# IO_Systems.net
KiCad netlist of a schematic drawn in Altium Designer
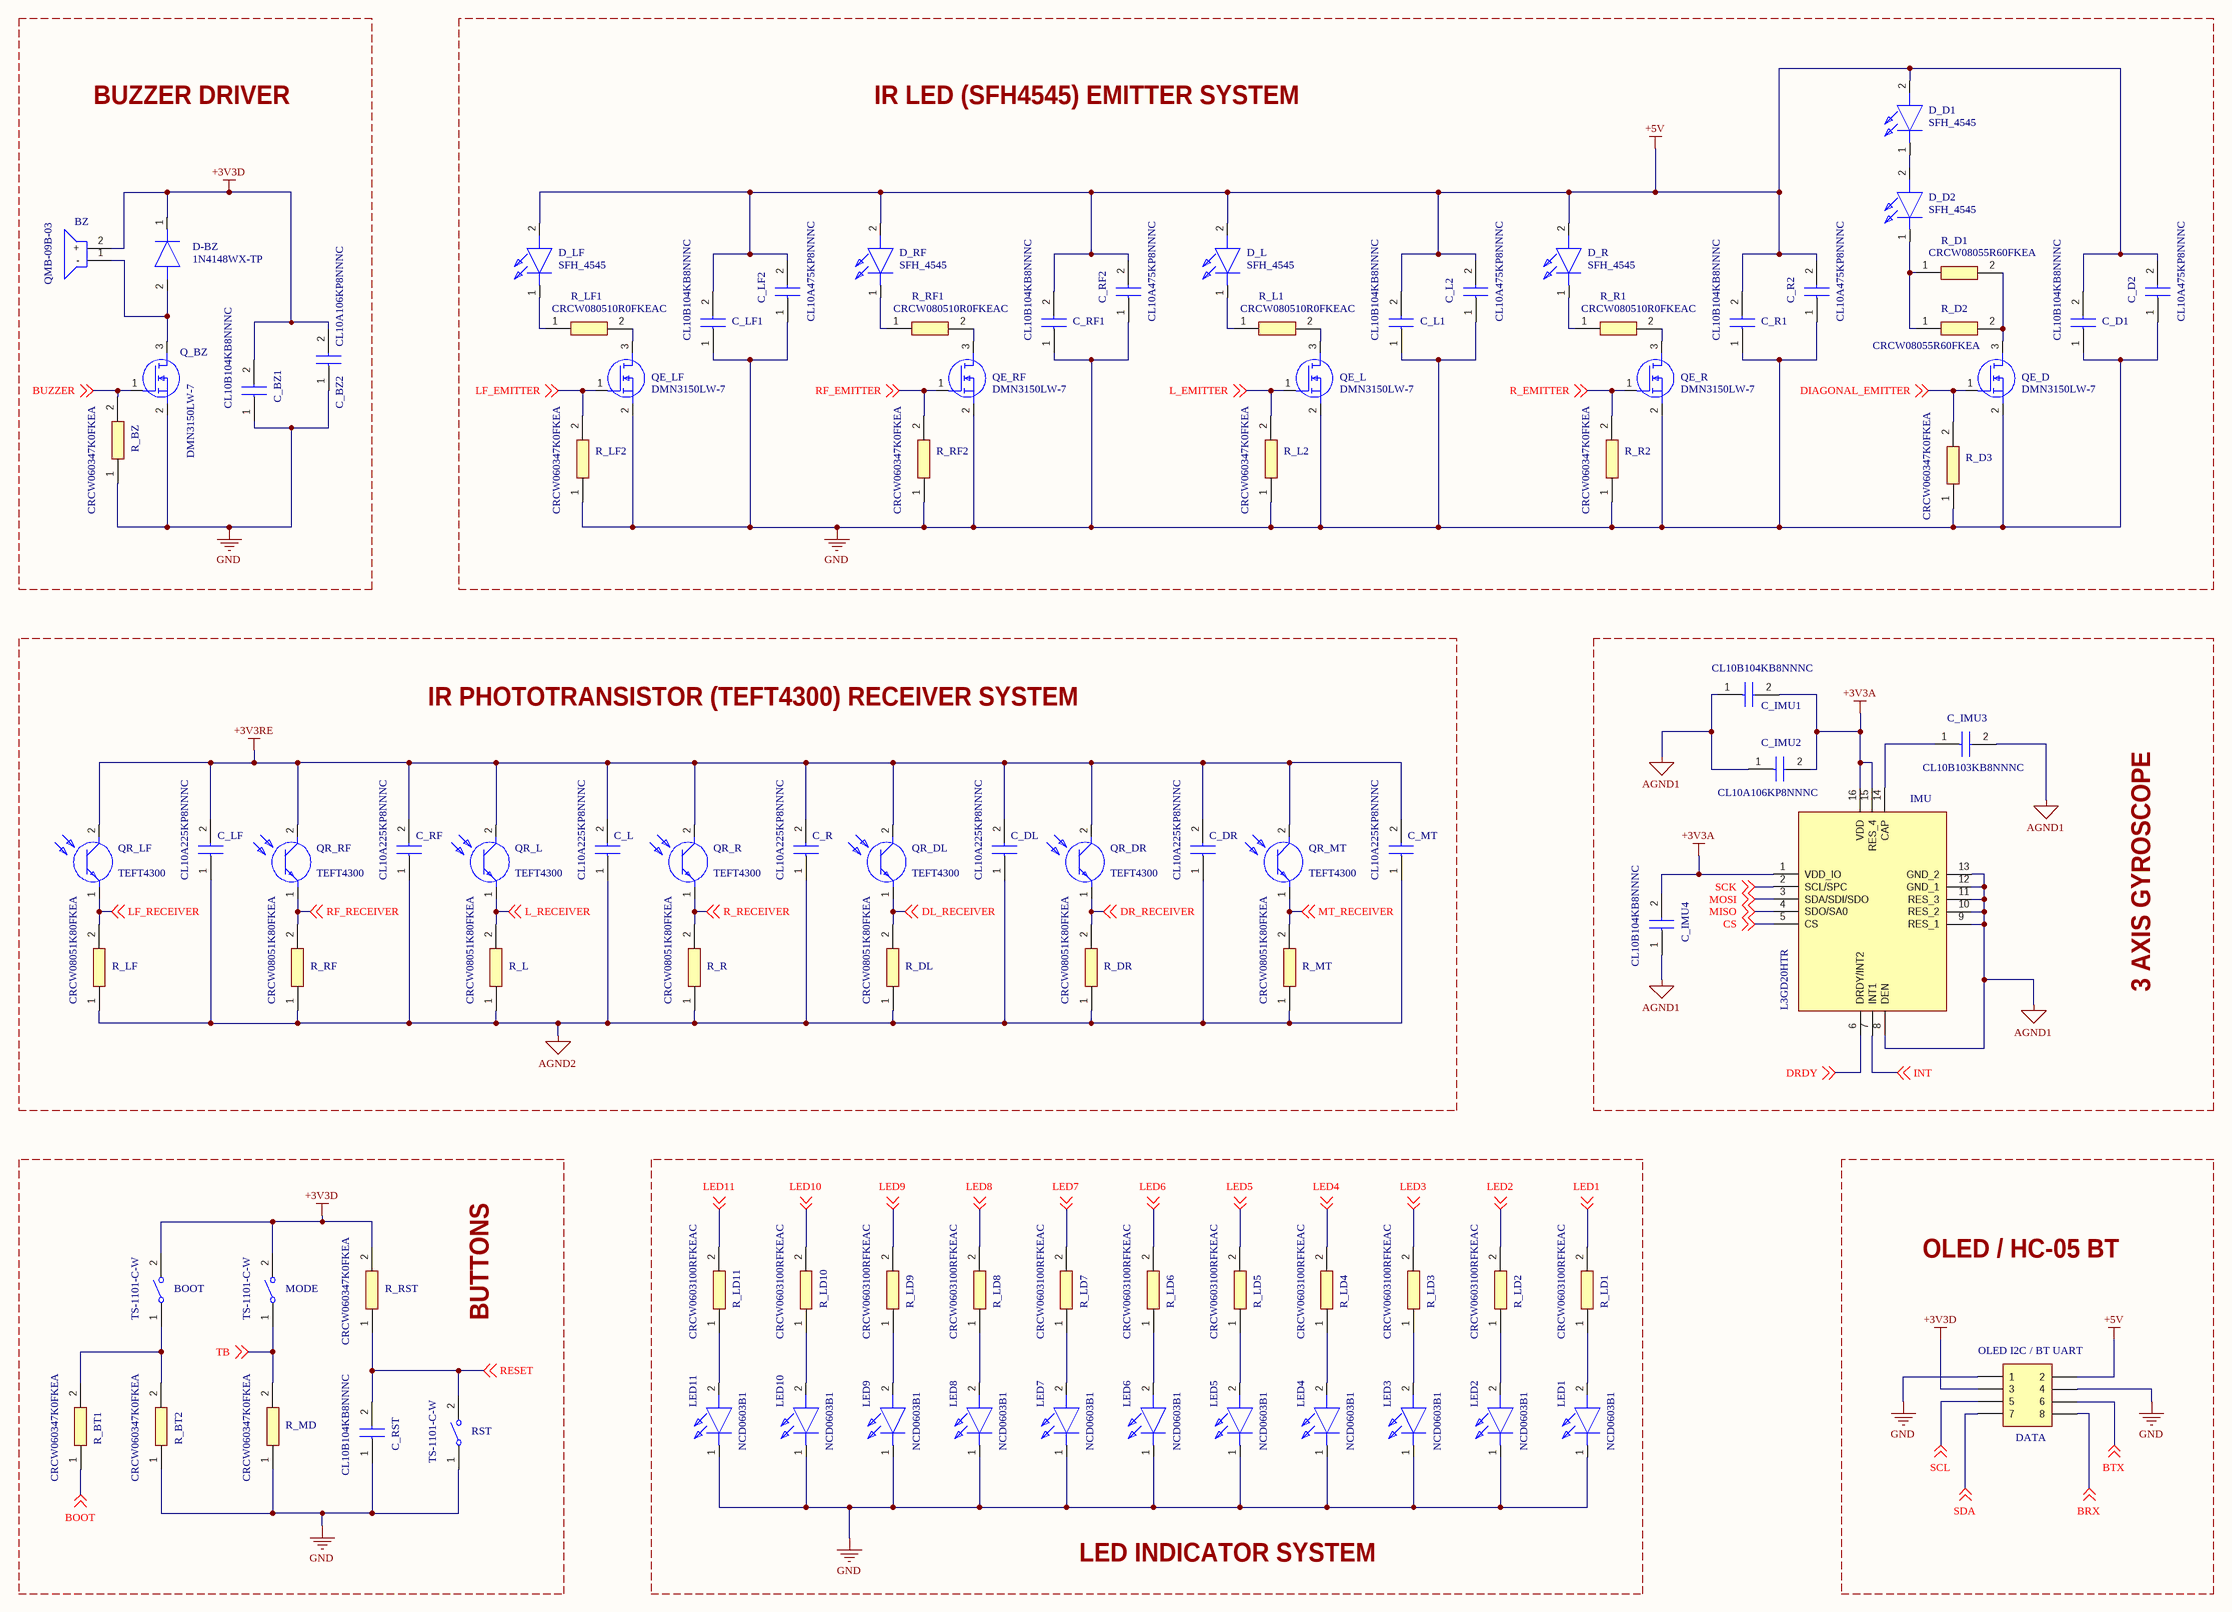
[diagram p0: IO Systems.SchDoc]

(export (version "E")
  (design (tool "Eeschema 10.0.6"))
  (components
    (comp (ref "BOOT")
      (value "TS-1101-C-W")
      (footprint "TECO-FSMSM-2_V")
      (fields (field (name "MANUFACTURER") "TE Connectivity"))
      (libsource (lib "Altium Content Vault") (part "SW-SPST-2_C"))
    )
    (comp (ref "BZ")
      (value "QMB-09B-03")
      (footprint "SamacSys:CST931AP")
      (description "85dB Passive (external drive) Electromagnetic Type 2.7kHz Plugin,D=9mm Buzzers ROHS")
      (fields
        (field (name "MANUFACTURER_PART_NUMBER") "CST-931AP")
        (field (name "MOUSER PART NUMBER") "490-CST-931AP")
      )
      (libsource (lib "*") (part "CST-931AP"))
    )
    (comp (ref "C_BZ1")
      (value "CL10B104KB8NNNC")
      (footprint "SamacSys:CAPC1608X90N")
      (description "Capacitor")
      (fields (field (name "MOUSER PART NUMBER") "187-CL10B104KB8NNNC"))
      (libsource (lib "*") (part "CL10B104KB8NNNC"))
    )
    (comp (ref "C_BZ2")
      (value "CL10A106KP8NNNC")
      (footprint "SamacSys:CAPC1608X90N")
      (description "Capacitor")
      (fields (field (name "MOUSER PART NUMBER") "187-CL10A106KP8NNNC"))
      (libsource (lib "*") (part "CL10A106KP8NNNC"))
    )
    (comp (ref "C_D1")
      (value "CL10B104KB8NNNC")
      (footprint "SamacSys:CAPC1608X90N")
      (description "Capacitor")
      (fields (field (name "MOUSER PART NUMBER") "187-CL10B104KB8NNNC"))
      (libsource (lib "*") (part "CL10B104KB8NNNC"))
    )
    (comp (ref "C_D2")
      (value "CL10A475KP8NNNC")
      (footprint "SamacSys:CAPC1608X90N")
      (description "Capacitor")
      (fields (field (name "MOUSER PART NUMBER") "187-CL10A475KP8NNNC"))
      (libsource (lib "*") (part "CL10A475KP8NNNC"))
    )
    (comp (ref "C_DL")
      (value "CL10A225KP8NNNC")
      (footprint "SamacSys:CAPC1608X90N")
      (description "Capacitor")
      (fields (field (name "MOUSER PART NUMBER") "187-CL10A225KP8NNNC"))
      (libsource (lib "*") (part "CL10A225KP8NNNC"))
    )
    (comp (ref "C_DR")
      (value "CL10A225KP8NNNC")
      (footprint "SamacSys:CAPC1608X90N")
      (description "Capacitor")
      (fields (field (name "MOUSER PART NUMBER") "187-CL10A225KP8NNNC"))
      (libsource (lib "*") (part "CL10A225KP8NNNC"))
    )
    (comp (ref "C_IMU1")
      (value "CL10B104KB8NNNC")
      (footprint "SamacSys:CAPC1608X90N")
      (description "Capacitor")
      (fields (field (name "MOUSER PART NUMBER") "187-CL10B104KB8NNNC"))
      (libsource (lib "*") (part "CL10B104KB8NNNC"))
    )
    (comp (ref "C_IMU2")
      (value "CL10A106KP8NNNC")
      (footprint "SamacSys:CAPC1608X90N")
      (description "Capacitor")
      (fields (field (name "MOUSER PART NUMBER") "187-CL10A106KP8NNNC"))
      (libsource (lib "*") (part "CL10A106KP8NNNC"))
    )
    (comp (ref "C_IMU3")
      (value "CL10B103KB8NNNC")
      (footprint "SamacSys:CAPC1608X90N")
      (description "Capacitor")
      (fields (field (name "MOUSER PART NUMBER") "187-CL10B103KB8NNNC"))
      (libsource (lib "*") (part "CL10B103KB8NNNC"))
    )
    (comp (ref "C_IMU4")
      (value "CL10B104KB8NNNC")
      (footprint "SamacSys:CAPC1608X90N")
      (description "Capacitor")
      (fields (field (name "MOUSER PART NUMBER") "187-CL10B104KB8NNNC"))
      (libsource (lib "*") (part "CL10B104KB8NNNC"))
    )
    (comp (ref "C_L")
      (value "CL10A225KP8NNNC")
      (footprint "SamacSys:CAPC1608X90N")
      (description "Capacitor")
      (fields (field (name "MOUSER PART NUMBER") "187-CL10A225KP8NNNC"))
      (libsource (lib "*") (part "CL10A225KP8NNNC"))
    )
    (comp (ref "C_L1")
      (value "CL10B104KB8NNNC")
      (footprint "SamacSys:CAPC1608X90N")
      (description "Capacitor")
      (fields (field (name "MOUSER PART NUMBER") "187-CL10B104KB8NNNC"))
      (libsource (lib "*") (part "CL10B104KB8NNNC"))
    )
    (comp (ref "C_L2")
      (value "CL10A475KP8NNNC")
      (footprint "SamacSys:CAPC1608X90N")
      (description "Capacitor")
      (fields (field (name "MOUSER PART NUMBER") "187-CL10A475KP8NNNC"))
      (libsource (lib "*") (part "CL10A475KP8NNNC"))
    )
    (comp (ref "C_LF")
      (value "CL10A225KP8NNNC")
      (footprint "SamacSys:CAPC1608X90N")
      (description "Capacitor")
      (fields (field (name "MOUSER PART NUMBER") "187-CL10A225KP8NNNC"))
      (libsource (lib "*") (part "CL10A225KP8NNNC"))
    )
    (comp (ref "C_LF1")
      (value "CL10B104KB8NNNC")
      (footprint "SamacSys:CAPC1608X90N")
      (description "Capacitor")
      (fields (field (name "MOUSER PART NUMBER") "187-CL10B104KB8NNNC"))
      (libsource (lib "*") (part "CL10B104KB8NNNC"))
    )
    (comp (ref "C_LF2")
      (value "CL10A475KP8NNNC")
      (footprint "SamacSys:CAPC1608X90N")
      (description "Capacitor")
      (fields (field (name "MOUSER PART NUMBER") "187-CL10A475KP8NNNC"))
      (libsource (lib "*") (part "CL10A475KP8NNNC"))
    )
    (comp (ref "C_MT")
      (value "CL10A225KP8NNNC")
      (footprint "SamacSys:CAPC1608X90N")
      (description "Capacitor")
      (fields (field (name "MOUSER PART NUMBER") "187-CL10A225KP8NNNC"))
      (libsource (lib "*") (part "CL10A225KP8NNNC"))
    )
    (comp (ref "C_R")
      (value "CL10A225KP8NNNC")
      (footprint "SamacSys:CAPC1608X90N")
      (description "Capacitor")
      (fields (field (name "MOUSER PART NUMBER") "187-CL10A225KP8NNNC"))
      (libsource (lib "*") (part "CL10A225KP8NNNC"))
    )
    (comp (ref "C_R1")
      (value "CL10B104KB8NNNC")
      (footprint "SamacSys:CAPC1608X90N")
      (description "Capacitor")
      (fields (field (name "MOUSER PART NUMBER") "187-CL10B104KB8NNNC"))
      (libsource (lib "*") (part "CL10B104KB8NNNC"))
    )
    (comp (ref "C_R2")
      (value "CL10A475KP8NNNC")
      (footprint "SamacSys:CAPC1608X90N")
      (description "Capacitor")
      (fields (field (name "MOUSER PART NUMBER") "187-CL10A475KP8NNNC"))
      (libsource (lib "*") (part "CL10A475KP8NNNC"))
    )
    (comp (ref "C_RF")
      (value "CL10A225KP8NNNC")
      (footprint "SamacSys:CAPC1608X90N")
      (description "Capacitor")
      (fields (field (name "MOUSER PART NUMBER") "187-CL10A225KP8NNNC"))
      (libsource (lib "*") (part "CL10A225KP8NNNC"))
    )
    (comp (ref "C_RF1")
      (value "CL10B104KB8NNNC")
      (footprint "SamacSys:CAPC1608X90N")
      (description "Capacitor")
      (fields (field (name "MOUSER PART NUMBER") "187-CL10B104KB8NNNC"))
      (libsource (lib "*") (part "CL10B104KB8NNNC"))
    )
    (comp (ref "C_RF2")
      (value "CL10A475KP8NNNC")
      (footprint "SamacSys:CAPC1608X90N")
      (description "Capacitor")
      (fields (field (name "MOUSER PART NUMBER") "187-CL10A475KP8NNNC"))
      (libsource (lib "*") (part "CL10A475KP8NNNC"))
    )
    (comp (ref "C_RST")
      (value "CL10B104KB8NNNC")
      (footprint "SamacSys:CAPC1608X90N")
      (description "Capacitor")
      (fields (field (name "MOUSER PART NUMBER") "187-CL10B104KB8NNNC"))
      (libsource (lib "*") (part "CL10B104KB8NNNC"))
    )
    (comp (ref "D-BZ")
      (value "1N4148WX-TP")
      (footprint "SamacSys:SOD2512X115N")
      (description "Diode")
      (fields (field (name "MOUSER PART NUMBER") "833-1N4148WX-TP"))
      (libsource (lib "*") (part "1N4148WX-TP"))
    )
    (comp (ref "DATA")
      (value "OLED I2C / BT UART")
      (footprint "MY_FE04-2")
      (description "Header, 8-Pin, Dual row")
      (fields (field (name "ASID PART NUMBER") "Header 4X2-AS"))
      (libsource (lib "Mylib+Rev+4") (part "Header 4X2"))
    )
    (comp (ref "D_D1")
      (value "SFH_4545")
      (footprint "SamacSys:SFH4545")
      (description "LED")
      (fields
        (field (name "MANUFACTURER_PART_NUMBER") "SFH 4545")
        (field (name "MOUSER PART NUMBER") "720-SFH4545")
      )
      (libsource (lib "*") (part "SFH_4545"))
    )
    (comp (ref "D_D2")
      (value "SFH_4545")
      (footprint "SamacSys:SFH4545")
      (description "LED")
      (fields
        (field (name "MANUFACTURER_PART_NUMBER") "SFH 4545")
        (field (name "MOUSER PART NUMBER") "720-SFH4545")
      )
      (libsource (lib "*") (part "SFH_4545"))
    )
    (comp (ref "D_L")
      (value "SFH_4545")
      (footprint "SamacSys:SFH4545")
      (description "LED")
      (fields
        (field (name "MANUFACTURER_PART_NUMBER") "SFH 4545")
        (field (name "MOUSER PART NUMBER") "720-SFH4545")
      )
      (libsource (lib "*") (part "SFH_4545"))
    )
    (comp (ref "D_LF")
      (value "SFH_4545")
      (footprint "SamacSys:SFH4545")
      (description "LED")
      (fields
        (field (name "MANUFACTURER_PART_NUMBER") "SFH 4545")
        (field (name "MOUSER PART NUMBER") "720-SFH4545")
      )
      (libsource (lib "*") (part "SFH_4545"))
    )
    (comp (ref "D_R")
      (value "SFH_4545")
      (footprint "SamacSys:SFH4545")
      (description "LED")
      (fields
        (field (name "MANUFACTURER_PART_NUMBER") "SFH 4545")
        (field (name "MOUSER PART NUMBER") "720-SFH4545")
      )
      (libsource (lib "*") (part "SFH_4545"))
    )
    (comp (ref "D_RF")
      (value "SFH_4545")
      (footprint "SamacSys:SFH4545")
      (description "LED")
      (fields
        (field (name "MANUFACTURER_PART_NUMBER") "SFH 4545")
        (field (name "MOUSER PART NUMBER") "720-SFH4545")
      )
      (libsource (lib "*") (part "SFH_4545"))
    )
    (comp (ref "IMU")
      (value "L3GD20HTR")
      (footprint "SamacSys:H3LIS100DLTR")
      (description "Integrated Circuit")
      (fields (field (name "MOUSER PART NUMBER") "511-L3GD20HTR"))
      (libsource (lib "*") (part "L3GD20HTR"))
    )
    (comp (ref "LED1")
      (value "NCD0603B1")
      (footprint "SamacSys:LEDC1608X40N")
      (fields
        (field (name "MANUFACTURER_PART_NUMBER") "LB Q39E-L2OO-35-1")
        (field (name "MOUSER PART NUMBER") "720-LBQ39EL2N2351")
      )
      (libsource (lib "*") (part "LB_Q39E-L2OO-35-1"))
    )
    (comp (ref "LED2")
      (value "NCD0603B1")
      (footprint "SamacSys:LEDC1608X40N")
      (fields
        (field (name "MANUFACTURER_PART_NUMBER") "LB Q39E-L2OO-35-1")
        (field (name "MOUSER PART NUMBER") "720-LBQ39EL2N2351")
      )
      (libsource (lib "*") (part "LB_Q39E-L2OO-35-1"))
    )
    (comp (ref "LED3")
      (value "NCD0603B1")
      (footprint "SamacSys:LEDC1608X40N")
      (fields
        (field (name "MANUFACTURER_PART_NUMBER") "LB Q39E-L2OO-35-1")
        (field (name "MOUSER PART NUMBER") "720-LBQ39EL2N2351")
      )
      (libsource (lib "*") (part "LB_Q39E-L2OO-35-1"))
    )
    (comp (ref "LED4")
      (value "NCD0603B1")
      (footprint "SamacSys:LEDC1608X40N")
      (fields
        (field (name "MANUFACTURER_PART_NUMBER") "LB Q39E-L2OO-35-1")
        (field (name "MOUSER PART NUMBER") "720-LBQ39EL2N2351")
      )
      (libsource (lib "*") (part "LB_Q39E-L2OO-35-1"))
    )
    (comp (ref "LED5")
      (value "NCD0603B1")
      (footprint "SamacSys:LEDC1608X40N")
      (fields
        (field (name "MANUFACTURER_PART_NUMBER") "LB Q39E-L2OO-35-1")
        (field (name "MOUSER PART NUMBER") "720-LBQ39EL2N2351")
      )
      (libsource (lib "*") (part "LB_Q39E-L2OO-35-1"))
    )
    (comp (ref "LED6")
      (value "NCD0603B1")
      (footprint "SamacSys:LEDC1608X40N")
      (fields
        (field (name "MANUFACTURER_PART_NUMBER") "LB Q39E-L2OO-35-1")
        (field (name "MOUSER PART NUMBER") "720-LBQ39EL2N2351")
      )
      (libsource (lib "*") (part "LB_Q39E-L2OO-35-1"))
    )
    (comp (ref "LED7")
      (value "NCD0603B1")
      (footprint "SamacSys:LEDC1608X40N")
      (fields
        (field (name "MANUFACTURER_PART_NUMBER") "LB Q39E-L2OO-35-1")
        (field (name "MOUSER PART NUMBER") "720-LBQ39EL2N2351")
      )
      (libsource (lib "*") (part "LB_Q39E-L2OO-35-1"))
    )
    (comp (ref "LED8")
      (value "NCD0603B1")
      (footprint "SamacSys:LEDC1608X40N")
      (fields
        (field (name "MANUFACTURER_PART_NUMBER") "LB Q39E-L2OO-35-1")
        (field (name "MOUSER PART NUMBER") "720-LBQ39EL2N2351")
      )
      (libsource (lib "*") (part "LB_Q39E-L2OO-35-1"))
    )
    (comp (ref "LED9")
      (value "NCD0603B1")
      (footprint "SamacSys:LEDC1608X40N")
      (fields
        (field (name "MANUFACTURER_PART_NUMBER") "LB Q39E-L2OO-35-1")
        (field (name "MOUSER PART NUMBER") "720-LBQ39EL2N2351")
      )
      (libsource (lib "*") (part "LB_Q39E-L2OO-35-1"))
    )
    (comp (ref "LED10")
      (value "NCD0603B1")
      (footprint "SamacSys:LEDC1608X40N")
      (fields
        (field (name "MANUFACTURER_PART_NUMBER") "LB Q39E-L2OO-35-1")
        (field (name "MOUSER PART NUMBER") "720-LBQ39EL2N2351")
      )
      (libsource (lib "*") (part "LB_Q39E-L2OO-35-1"))
    )
    (comp (ref "LED11")
      (value "NCD0603B1")
      (footprint "SamacSys:LEDC1608X40N")
      (fields
        (field (name "MANUFACTURER_PART_NUMBER") "LB Q39E-L2OO-35-1")
        (field (name "MOUSER PART NUMBER") "720-LBQ39EL2N2351")
      )
      (libsource (lib "*") (part "LB_Q39E-L2OO-35-1"))
    )
    (comp (ref "MODE")
      (value "TS-1101-C-W")
      (footprint "TECO-FSMSM-2_V")
      (fields (field (name "MANUFACTURER") "TE Connectivity"))
      (libsource (lib "Altium Content Vault") (part "SW-SPST-2_C"))
    )
    (comp (ref "QE_D")
      (value "DMN3150LW-7")
      (footprint "SamacSys:SOT65P210X110-3N")
      (description "MOSFET (N-Channel)")
      (fields (field (name "MOUSER PART NUMBER") "621-DMN3150LW-7"))
      (libsource (lib "*") (part "DMN3150LW-7"))
    )
    (comp (ref "QE_L")
      (value "DMN3150LW-7")
      (footprint "SamacSys:SOT65P210X110-3N")
      (description "MOSFET (N-Channel)")
      (fields (field (name "MOUSER PART NUMBER") "621-DMN3150LW-7"))
      (libsource (lib "*") (part "DMN3150LW-7"))
    )
    (comp (ref "QE_LF")
      (value "DMN3150LW-7")
      (footprint "SamacSys:SOT65P210X110-3N")
      (description "MOSFET (N-Channel)")
      (fields (field (name "MOUSER PART NUMBER") "621-DMN3150LW-7"))
      (libsource (lib "*") (part "DMN3150LW-7"))
    )
    (comp (ref "QE_R")
      (value "DMN3150LW-7")
      (footprint "SamacSys:SOT65P210X110-3N")
      (description "MOSFET (N-Channel)")
      (fields (field (name "MOUSER PART NUMBER") "621-DMN3150LW-7"))
      (libsource (lib "*") (part "DMN3150LW-7"))
    )
    (comp (ref "QE_RF")
      (value "DMN3150LW-7")
      (footprint "SamacSys:SOT65P210X110-3N")
      (description "MOSFET (N-Channel)")
      (fields (field (name "MOUSER PART NUMBER") "621-DMN3150LW-7"))
      (libsource (lib "*") (part "DMN3150LW-7"))
    )
    (comp (ref "QR_DL")
      (value "TEFT4300")
      (footprint "SamacSys:TEFT4300")
      (description "Phototransistor")
      (fields (field (name "MOUSER PART NUMBER") "782-TEFT4300"))
      (libsource (lib "*") (part "TEFT4300"))
    )
    (comp (ref "QR_DR")
      (value "TEFT4300")
      (footprint "SamacSys:TEFT4300")
      (description "Phototransistor")
      (fields (field (name "MOUSER PART NUMBER") "782-TEFT4300"))
      (libsource (lib "*") (part "TEFT4300"))
    )
    (comp (ref "QR_L")
      (value "TEFT4300")
      (footprint "SamacSys:TEFT4300")
      (description "Phototransistor")
      (fields (field (name "MOUSER PART NUMBER") "782-TEFT4300"))
      (libsource (lib "*") (part "TEFT4300"))
    )
    (comp (ref "QR_LF")
      (value "TEFT4300")
      (footprint "SamacSys:TEFT4300")
      (description "Phototransistor")
      (fields (field (name "MOUSER PART NUMBER") "782-TEFT4300"))
      (libsource (lib "*") (part "TEFT4300"))
    )
    (comp (ref "QR_MT")
      (value "TEFT4300")
      (footprint "SamacSys:TEFT4300")
      (description "Phototransistor")
      (fields (field (name "MOUSER PART NUMBER") "782-TEFT4300"))
      (libsource (lib "*") (part "TEFT4300"))
    )
    (comp (ref "QR_R")
      (value "TEFT4300")
      (footprint "SamacSys:TEFT4300")
      (description "Phototransistor")
      (fields (field (name "MOUSER PART NUMBER") "782-TEFT4300"))
      (libsource (lib "*") (part "TEFT4300"))
    )
    (comp (ref "QR_RF")
      (value "TEFT4300")
      (footprint "SamacSys:TEFT4300")
      (description "Phototransistor")
      (fields (field (name "MOUSER PART NUMBER") "782-TEFT4300"))
      (libsource (lib "*") (part "TEFT4300"))
    )
    (comp (ref "Q_BZ")
      (value "DMN3150LW-7")
      (footprint "SamacSys:SOT65P210X110-3N")
      (description "MOSFET (N-Channel)")
      (fields (field (name "MOUSER PART NUMBER") "621-DMN3150LW-7"))
      (libsource (lib "*") (part "DMN3150LW-7"))
    )
    (comp (ref "RST")
      (value "TS-1101-C-W")
      (footprint "TECO-FSMSM-2_V")
      (fields (field (name "MANUFACTURER") "TE Connectivity"))
      (libsource (lib "Altium Content Vault") (part "SW-SPST-2_C"))
    )
    (comp (ref "R_BT1")
      (value "CRCW060347K0FKEA")
      (footprint "SamacSys:RESC1608X50N")
      (description "Resistor")
      (fields (field (name "MOUSER PART NUMBER") "71-CRCW0603-47K-E3"))
      (libsource (lib "*") (part "CRCW060347K0FKEA"))
    )
    (comp (ref "R_BT2")
      (value "CRCW060347K0FKEA")
      (footprint "SamacSys:RESC1608X50N")
      (description "Resistor")
      (fields (field (name "MOUSER PART NUMBER") "71-CRCW0603-47K-E3"))
      (libsource (lib "*") (part "CRCW060347K0FKEA"))
    )
    (comp (ref "R_BZ")
      (value "CRCW060347K0FKEA")
      (footprint "SamacSys:RESC1608X50N")
      (description "Resistor")
      (fields (field (name "MOUSER PART NUMBER") "71-CRCW0603-47K-E3"))
      (libsource (lib "*") (part "CRCW060347K0FKEA"))
    )
    (comp (ref "R_D1")
      (value "CRCW08055R60FKEA")
      (footprint "SamacSys:RESC2012X60N")
      (description "Resistor")
      (fields
        (field (name "MANUFACTURER_PART_NUMBER") "CRCW08055R60FKEAHP")
        (field (name "MOUSER PART NUMBER") "71-CRCW08055R60FKEAH")
      )
      (libsource (lib "*") (part "CRCW08055R60FKEAHP"))
    )
    (comp (ref "R_D2")
      (value "CRCW08055R60FKEA")
      (footprint "SamacSys:RESC2012X60N")
      (description "Resistor")
      (fields
        (field (name "MANUFACTURER_PART_NUMBER") "CRCW08055R60FKEAHP")
        (field (name "MOUSER PART NUMBER") "71-CRCW08055R60FKEAH")
      )
      (libsource (lib "*") (part "CRCW08055R60FKEAHP"))
    )
    (comp (ref "R_D3")
      (value "CRCW060347K0FKEA")
      (footprint "SamacSys:RESC1608X50N")
      (description "Resistor")
      (fields (field (name "MOUSER PART NUMBER") "71-CRCW0603-47K-E3"))
      (libsource (lib "*") (part "CRCW060347K0FKEA"))
    )
    (comp (ref "R_DL")
      (value "CRCW08051K80FKEA")
      (footprint "SamacSys:RESC2012X60N")
      (description "Resistor")
      (fields
        (field (name "MANUFACTURER_PART_NUMBER") "CRCW08051K80FKEAC")
        (field (name "MOUSER PART NUMBER") "71-CRCW08051K80FKEAC")
      )
      (libsource (lib "*") (part "CRCW08051K80FKEAC"))
    )
    (comp (ref "R_DR")
      (value "CRCW08051K80FKEA")
      (footprint "SamacSys:RESC2012X60N")
      (description "Resistor")
      (fields
        (field (name "MANUFACTURER_PART_NUMBER") "CRCW08051K80FKEAC")
        (field (name "MOUSER PART NUMBER") "71-CRCW08051K80FKEAC")
      )
      (libsource (lib "*") (part "CRCW08051K80FKEAC"))
    )
    (comp (ref "R_L")
      (value "CRCW08051K80FKEA")
      (footprint "SamacSys:RESC2012X60N")
      (description "Resistor")
      (fields
        (field (name "MANUFACTURER_PART_NUMBER") "CRCW08051K80FKEAC")
        (field (name "MOUSER PART NUMBER") "71-CRCW08051K80FKEAC")
      )
      (libsource (lib "*") (part "CRCW08051K80FKEAC"))
    )
    (comp (ref "R_L1")
      (value "CRCW080510R0FKEAC")
      (footprint "SamacSys:RESC2012X60N")
      (description "Resistor")
      (fields (field (name "MOUSER PART NUMBER") "71-CRCW080510R0FKEAC"))
      (libsource (lib "*") (part "CRCW080510R0FKEAC"))
    )
    (comp (ref "R_L2")
      (value "CRCW060347K0FKEA")
      (footprint "SamacSys:RESC1608X50N")
      (description "Resistor")
      (fields (field (name "MOUSER PART NUMBER") "71-CRCW0603-47K-E3"))
      (libsource (lib "*") (part "CRCW060347K0FKEA"))
    )
    (comp (ref "R_LD1")
      (value "CRCW0603100RFKEAC")
      (footprint "SamacSys:RESC1608X55N")
      (description "Resistor")
      (fields (field (name "MOUSER PART NUMBER") "71-CRCW0603100RFKEAC"))
      (libsource (lib "*") (part "CRCW0603100RFKEAC"))
    )
    (comp (ref "R_LD2")
      (value "CRCW0603100RFKEAC")
      (footprint "SamacSys:RESC1608X55N")
      (description "Resistor")
      (fields (field (name "MOUSER PART NUMBER") "71-CRCW0603100RFKEAC"))
      (libsource (lib "*") (part "CRCW0603100RFKEAC"))
    )
    (comp (ref "R_LD3")
      (value "CRCW0603100RFKEAC")
      (footprint "SamacSys:RESC1608X55N")
      (description "Resistor")
      (fields (field (name "MOUSER PART NUMBER") "71-CRCW0603100RFKEAC"))
      (libsource (lib "*") (part "CRCW0603100RFKEAC"))
    )
    (comp (ref "R_LD4")
      (value "CRCW0603100RFKEAC")
      (footprint "SamacSys:RESC1608X55N")
      (description "Resistor")
      (fields (field (name "MOUSER PART NUMBER") "71-CRCW0603100RFKEAC"))
      (libsource (lib "*") (part "CRCW0603100RFKEAC"))
    )
    (comp (ref "R_LD5")
      (value "CRCW0603100RFKEAC")
      (footprint "SamacSys:RESC1608X55N")
      (description "Resistor")
      (fields (field (name "MOUSER PART NUMBER") "71-CRCW0603100RFKEAC"))
      (libsource (lib "*") (part "CRCW0603100RFKEAC"))
    )
    (comp (ref "R_LD6")
      (value "CRCW0603100RFKEAC")
      (footprint "SamacSys:RESC1608X55N")
      (description "Resistor")
      (fields (field (name "MOUSER PART NUMBER") "71-CRCW0603100RFKEAC"))
      (libsource (lib "*") (part "CRCW0603100RFKEAC"))
    )
    (comp (ref "R_LD7")
      (value "CRCW0603100RFKEAC")
      (footprint "SamacSys:RESC1608X55N")
      (description "Resistor")
      (fields (field (name "MOUSER PART NUMBER") "71-CRCW0603100RFKEAC"))
      (libsource (lib "*") (part "CRCW0603100RFKEAC"))
    )
    (comp (ref "R_LD8")
      (value "CRCW0603100RFKEAC")
      (footprint "SamacSys:RESC1608X55N")
      (description "Resistor")
      (fields (field (name "MOUSER PART NUMBER") "71-CRCW0603100RFKEAC"))
      (libsource (lib "*") (part "CRCW0603100RFKEAC"))
    )
    (comp (ref "R_LD9")
      (value "CRCW0603100RFKEAC")
      (footprint "SamacSys:RESC1608X55N")
      (description "Resistor")
      (fields (field (name "MOUSER PART NUMBER") "71-CRCW0603100RFKEAC"))
      (libsource (lib "*") (part "CRCW0603100RFKEAC"))
    )
    (comp (ref "R_LD10")
      (value "CRCW0603100RFKEAC")
      (footprint "SamacSys:RESC1608X55N")
      (description "Resistor")
      (fields (field (name "MOUSER PART NUMBER") "71-CRCW0603100RFKEAC"))
      (libsource (lib "*") (part "CRCW0603100RFKEAC"))
    )
    (comp (ref "R_LD11")
      (value "CRCW0603100RFKEAC")
      (footprint "SamacSys:RESC1608X55N")
      (description "Resistor")
      (fields (field (name "MOUSER PART NUMBER") "71-CRCW0603100RFKEAC"))
      (libsource (lib "*") (part "CRCW0603100RFKEAC"))
    )
    (comp (ref "R_LF")
      (value "CRCW08051K80FKEA")
      (footprint "SamacSys:RESC2012X60N")
      (description "Resistor")
      (fields
        (field (name "MANUFACTURER_PART_NUMBER") "CRCW08051K80FKEAC")
        (field (name "MOUSER PART NUMBER") "71-CRCW08051K80FKEAC")
      )
      (libsource (lib "*") (part "CRCW08051K80FKEAC"))
    )
    (comp (ref "R_LF1")
      (value "CRCW080510R0FKEAC")
      (footprint "SamacSys:RESC2012X60N")
      (description "Resistor")
      (fields (field (name "MOUSER PART NUMBER") "71-CRCW080510R0FKEAC"))
      (libsource (lib "*") (part "CRCW080510R0FKEAC"))
    )
    (comp (ref "R_LF2")
      (value "CRCW060347K0FKEA")
      (footprint "SamacSys:RESC1608X50N")
      (description "Resistor")
      (fields (field (name "MOUSER PART NUMBER") "71-CRCW0603-47K-E3"))
      (libsource (lib "*") (part "CRCW060347K0FKEA"))
    )
    (comp (ref "R_MD")
      (value "CRCW060347K0FKEA")
      (footprint "SamacSys:RESC1608X50N")
      (description "Resistor")
      (fields (field (name "MOUSER PART NUMBER") "71-CRCW0603-47K-E3"))
      (libsource (lib "*") (part "CRCW060347K0FKEA"))
    )
    (comp (ref "R_MT")
      (value "CRCW08051K80FKEA")
      (footprint "SamacSys:RESC2012X60N")
      (description "Resistor")
      (fields
        (field (name "MANUFACTURER_PART_NUMBER") "CRCW08051K80FKEAC")
        (field (name "MOUSER PART NUMBER") "71-CRCW08051K80FKEAC")
      )
      (libsource (lib "*") (part "CRCW08051K80FKEAC"))
    )
    (comp (ref "R_R")
      (value "CRCW08051K80FKEA")
      (footprint "SamacSys:RESC2012X60N")
      (description "Resistor")
      (fields
        (field (name "MANUFACTURER_PART_NUMBER") "CRCW08051K80FKEAC")
        (field (name "MOUSER PART NUMBER") "71-CRCW08051K80FKEAC")
      )
      (libsource (lib "*") (part "CRCW08051K80FKEAC"))
    )
    (comp (ref "R_R1")
      (value "CRCW080510R0FKEAC")
      (footprint "SamacSys:RESC2012X60N")
      (description "Resistor")
      (fields (field (name "MOUSER PART NUMBER") "71-CRCW080510R0FKEAC"))
      (libsource (lib "*") (part "CRCW080510R0FKEAC"))
    )
    (comp (ref "R_R2")
      (value "CRCW060347K0FKEA")
      (footprint "SamacSys:RESC1608X50N")
      (description "Resistor")
      (fields (field (name "MOUSER PART NUMBER") "71-CRCW0603-47K-E3"))
      (libsource (lib "*") (part "CRCW060347K0FKEA"))
    )
    (comp (ref "R_RF")
      (value "CRCW08051K80FKEA")
      (footprint "SamacSys:RESC2012X60N")
      (description "Resistor")
      (fields
        (field (name "MANUFACTURER_PART_NUMBER") "CRCW08051K80FKEAC")
        (field (name "MOUSER PART NUMBER") "71-CRCW08051K80FKEAC")
      )
      (libsource (lib "*") (part "CRCW08051K80FKEAC"))
    )
    (comp (ref "R_RF1")
      (value "CRCW080510R0FKEAC")
      (footprint "SamacSys:RESC2012X60N")
      (description "Resistor")
      (fields (field (name "MOUSER PART NUMBER") "71-CRCW080510R0FKEAC"))
      (libsource (lib "*") (part "CRCW080510R0FKEAC"))
    )
    (comp (ref "R_RF2")
      (value "CRCW060347K0FKEA")
      (footprint "SamacSys:RESC1608X50N")
      (description "Resistor")
      (fields (field (name "MOUSER PART NUMBER") "71-CRCW0603-47K-E3"))
      (libsource (lib "*") (part "CRCW060347K0FKEA"))
    )
    (comp (ref "R_RST")
      (value "CRCW060347K0FKEA")
      (footprint "SamacSys:RESC1608X50N")
      (description "Resistor")
      (fields (field (name "MOUSER PART NUMBER") "71-CRCW0603-47K-E3"))
      (libsource (lib "*") (part "CRCW060347K0FKEA"))
    )
  )
  (nets
    (net (code "1") (name "+3V3A") (class "Default")
      (node (ref "C_IMU1") (pin "2") (pinfunction "2_2") (pintype "passive"))
      (node (ref "C_IMU2") (pin "2") (pinfunction "2_2") (pintype "passive"))
      (node (ref "C_IMU4") (pin "2") (pinfunction "2_2") (pintype "passive"))
      (node (ref "IMU") (pin "1") (pinfunction "VDD_IO_1") (pintype "passive"))
      (node (ref "IMU") (pin "15") (pinfunction "RES_4_15") (pintype "passive"))
      (node (ref "IMU") (pin "16") (pinfunction "VDD_16") (pintype "passive"))
    )
    (net (code "2") (name "+3V3D") (class "Default")
      (node (ref "BOOT") (pin "2") (pinfunction "2_2") (pintype "passive"))
      (node (ref "BZ") (pin "2") (pinfunction "+_2") (pintype "passive"))
      (node (ref "C_BZ1") (pin "2") (pinfunction "2_2") (pintype "passive"))
      (node (ref "C_BZ2") (pin "2") (pinfunction "2_2") (pintype "passive"))
      (node (ref "D-BZ") (pin "1") (pinfunction "K_1") (pintype "passive"))
      (node (ref "DATA") (pin "3") (pinfunction "3_3") (pintype "passive"))
      (node (ref "MODE") (pin "2") (pinfunction "2_2") (pintype "passive"))
      (node (ref "R_RST") (pin "2") (pinfunction "2_2") (pintype "passive"))
    )
    (net (code "3") (name "+3V3RE") (class "Default")
      (node (ref "C_DL") (pin "2") (pinfunction "2_2") (pintype "passive"))
      (node (ref "C_DR") (pin "2") (pinfunction "2_2") (pintype "passive"))
      (node (ref "C_L") (pin "2") (pinfunction "2_2") (pintype "passive"))
      (node (ref "C_LF") (pin "2") (pinfunction "2_2") (pintype "passive"))
      (node (ref "C_MT") (pin "2") (pinfunction "2_2") (pintype "passive"))
      (node (ref "C_R") (pin "2") (pinfunction "2_2") (pintype "passive"))
      (node (ref "C_RF") (pin "2") (pinfunction "2_2") (pintype "passive"))
      (node (ref "QR_DL") (pin "2") (pinfunction "C_2") (pintype "passive"))
      (node (ref "QR_DR") (pin "2") (pinfunction "C_2") (pintype "passive"))
      (node (ref "QR_L") (pin "2") (pinfunction "C_2") (pintype "passive"))
      (node (ref "QR_LF") (pin "2") (pinfunction "C_2") (pintype "passive"))
      (node (ref "QR_MT") (pin "2") (pinfunction "C_2") (pintype "passive"))
      (node (ref "QR_R") (pin "2") (pinfunction "C_2") (pintype "passive"))
      (node (ref "QR_RF") (pin "2") (pinfunction "C_2") (pintype "passive"))
    )
    (net (code "4") (name "+5V") (class "Default")
      (node (ref "C_D1") (pin "2") (pinfunction "2_2") (pintype "passive"))
      (node (ref "C_D2") (pin "2") (pinfunction "2_2") (pintype "passive"))
      (node (ref "C_L1") (pin "2") (pinfunction "2_2") (pintype "passive"))
      (node (ref "C_L2") (pin "2") (pinfunction "2_2") (pintype "passive"))
      (node (ref "C_LF1") (pin "2") (pinfunction "2_2") (pintype "passive"))
      (node (ref "C_LF2") (pin "2") (pinfunction "2_2") (pintype "passive"))
      (node (ref "C_R1") (pin "2") (pinfunction "2_2") (pintype "passive"))
      (node (ref "C_R2") (pin "2") (pinfunction "2_2") (pintype "passive"))
      (node (ref "C_RF1") (pin "2") (pinfunction "2_2") (pintype "passive"))
      (node (ref "C_RF2") (pin "2") (pinfunction "2_2") (pintype "passive"))
      (node (ref "DATA") (pin "2") (pinfunction "2_2") (pintype "passive"))
      (node (ref "D_D1") (pin "2") (pinfunction "A_2") (pintype "passive"))
      (node (ref "D_L") (pin "2") (pinfunction "A_2") (pintype "passive"))
      (node (ref "D_LF") (pin "2") (pinfunction "A_2") (pintype "passive"))
      (node (ref "D_R") (pin "2") (pinfunction "A_2") (pintype "passive"))
      (node (ref "D_RF") (pin "2") (pinfunction "A_2") (pintype "passive"))
    )
    (net (code "5") (name "AGND1") (class "Default")
      (node (ref "C_IMU1") (pin "1") (pinfunction "1_1") (pintype "passive"))
      (node (ref "C_IMU2") (pin "1") (pinfunction "1_1") (pintype "passive"))
      (node (ref "C_IMU3") (pin "2") (pinfunction "2_2") (pintype "passive"))
      (node (ref "C_IMU4") (pin "1") (pinfunction "1_1") (pintype "passive"))
      (node (ref "IMU") (pin "10") (pinfunction "RES_2_10") (pintype "passive"))
      (node (ref "IMU") (pin "11") (pinfunction "RES_3_11") (pintype "passive"))
      (node (ref "IMU") (pin "12") (pinfunction "GND_1_12") (pintype "passive"))
      (node (ref "IMU") (pin "13") (pinfunction "GND_2_13") (pintype "passive"))
      (node (ref "IMU") (pin "8") (pinfunction "DEN_8") (pintype "passive"))
      (node (ref "IMU") (pin "9") (pinfunction "RES_1_9") (pintype "passive"))
    )
    (net (code "6") (name "AGND2") (class "Default")
      (node (ref "C_DL") (pin "1") (pinfunction "1_1") (pintype "passive"))
      (node (ref "C_DR") (pin "1") (pinfunction "1_1") (pintype "passive"))
      (node (ref "C_L") (pin "1") (pinfunction "1_1") (pintype "passive"))
      (node (ref "C_LF") (pin "1") (pinfunction "1_1") (pintype "passive"))
      (node (ref "C_MT") (pin "1") (pinfunction "1_1") (pintype "passive"))
      (node (ref "C_R") (pin "1") (pinfunction "1_1") (pintype "passive"))
      (node (ref "C_RF") (pin "1") (pinfunction "1_1") (pintype "passive"))
      (node (ref "R_DL") (pin "1") (pinfunction "1_1") (pintype "passive"))
      (node (ref "R_DR") (pin "1") (pinfunction "1_1") (pintype "passive"))
      (node (ref "R_L") (pin "1") (pinfunction "1_1") (pintype "passive"))
      (node (ref "R_LF") (pin "1") (pinfunction "1_1") (pintype "passive"))
      (node (ref "R_MT") (pin "1") (pinfunction "1_1") (pintype "passive"))
      (node (ref "R_R") (pin "1") (pinfunction "1_1") (pintype "passive"))
      (node (ref "R_RF") (pin "1") (pinfunction "1_1") (pintype "passive"))
    )
    (net (code "7") (name "BOOT") (class "Default")
      (node (ref "R_BT1") (pin "1") (pinfunction "1_1") (pintype "passive"))
    )
    (net (code "8") (name "BRX") (class "Default")
      (node (ref "DATA") (pin "8") (pinfunction "8_8") (pintype "passive"))
    )
    (net (code "9") (name "BTX") (class "Default")
      (node (ref "DATA") (pin "6") (pinfunction "6_6") (pintype "passive"))
    )
    (net (code "10") (name "BUZZER") (class "Default")
      (node (ref "Q_BZ") (pin "1") (pinfunction "G_1") (pintype "passive"))
      (node (ref "R_BZ") (pin "2") (pinfunction "2_2") (pintype "passive"))
    )
    (net (code "11") (name "CS") (class "Default")
      (node (ref "IMU") (pin "5") (pinfunction "CS_5") (pintype "passive"))
    )
    (net (code "12") (name "DIAGONAL_EMITTER") (class "Default")
      (node (ref "QE_D") (pin "1") (pinfunction "G_1") (pintype "passive"))
      (node (ref "R_D3") (pin "2") (pinfunction "2_2") (pintype "passive"))
    )
    (net (code "13") (name "DL_RECEIVER") (class "Default")
      (node (ref "QR_DL") (pin "1") (pinfunction "E_1") (pintype "passive"))
      (node (ref "R_DL") (pin "2") (pinfunction "2_2") (pintype "passive"))
    )
    (net (code "14") (name "DRDY") (class "Default")
      (node (ref "IMU") (pin "6") (pinfunction "DRDY/INT2_6") (pintype "passive"))
    )
    (net (code "15") (name "DR_RECEIVER") (class "Default")
      (node (ref "QR_DR") (pin "1") (pinfunction "E_1") (pintype "passive"))
      (node (ref "R_DR") (pin "2") (pinfunction "2_2") (pintype "passive"))
    )
    (net (code "16") (name "GND") (class "Default")
      (node (ref "C_BZ1") (pin "1") (pinfunction "1_1") (pintype "passive"))
      (node (ref "C_BZ2") (pin "1") (pinfunction "1_1") (pintype "passive"))
      (node (ref "C_D1") (pin "1") (pinfunction "1_1") (pintype "passive"))
      (node (ref "C_D2") (pin "1") (pinfunction "1_1") (pintype "passive"))
      (node (ref "C_L1") (pin "1") (pinfunction "1_1") (pintype "passive"))
      (node (ref "C_L2") (pin "1") (pinfunction "1_1") (pintype "passive"))
      (node (ref "C_LF1") (pin "1") (pinfunction "1_1") (pintype "passive"))
      (node (ref "C_LF2") (pin "1") (pinfunction "1_1") (pintype "passive"))
      (node (ref "C_R1") (pin "1") (pinfunction "1_1") (pintype "passive"))
      (node (ref "C_R2") (pin "1") (pinfunction "1_1") (pintype "passive"))
      (node (ref "C_RF1") (pin "1") (pinfunction "1_1") (pintype "passive"))
      (node (ref "C_RF2") (pin "1") (pinfunction "1_1") (pintype "passive"))
      (node (ref "C_RST") (pin "1") (pinfunction "1_1") (pintype "passive"))
      (node (ref "DATA") (pin "1") (pinfunction "1_1") (pintype "passive"))
      (node (ref "DATA") (pin "4") (pinfunction "4_4") (pintype "passive"))
      (node (ref "LED1") (pin "1") (pinfunction "K_1") (pintype "passive"))
      (node (ref "LED10") (pin "1") (pinfunction "K_1") (pintype "passive"))
      (node (ref "LED11") (pin "1") (pinfunction "K_1") (pintype "passive"))
      (node (ref "LED2") (pin "1") (pinfunction "K_1") (pintype "passive"))
      (node (ref "LED3") (pin "1") (pinfunction "K_1") (pintype "passive"))
      (node (ref "LED4") (pin "1") (pinfunction "K_1") (pintype "passive"))
      (node (ref "LED5") (pin "1") (pinfunction "K_1") (pintype "passive"))
      (node (ref "LED6") (pin "1") (pinfunction "K_1") (pintype "passive"))
      (node (ref "LED7") (pin "1") (pinfunction "K_1") (pintype "passive"))
      (node (ref "LED8") (pin "1") (pinfunction "K_1") (pintype "passive"))
      (node (ref "LED9") (pin "1") (pinfunction "K_1") (pintype "passive"))
      (node (ref "QE_D") (pin "2") (pinfunction "S_2") (pintype "passive"))
      (node (ref "QE_L") (pin "2") (pinfunction "S_2") (pintype "passive"))
      (node (ref "QE_LF") (pin "2") (pinfunction "S_2") (pintype "passive"))
      (node (ref "QE_R") (pin "2") (pinfunction "S_2") (pintype "passive"))
      (node (ref "QE_RF") (pin "2") (pinfunction "S_2") (pintype "passive"))
      (node (ref "Q_BZ") (pin "2") (pinfunction "S_2") (pintype "passive"))
      (node (ref "RST") (pin "1") (pinfunction "1_1") (pintype "passive"))
      (node (ref "R_BT2") (pin "1") (pinfunction "1_1") (pintype "passive"))
      (node (ref "R_BZ") (pin "1") (pinfunction "1_1") (pintype "passive"))
      (node (ref "R_D3") (pin "1") (pinfunction "1_1") (pintype "passive"))
      (node (ref "R_L2") (pin "1") (pinfunction "1_1") (pintype "passive"))
      (node (ref "R_LF2") (pin "1") (pinfunction "1_1") (pintype "passive"))
      (node (ref "R_MD") (pin "1") (pinfunction "1_1") (pintype "passive"))
      (node (ref "R_R2") (pin "1") (pinfunction "1_1") (pintype "passive"))
      (node (ref "R_RF2") (pin "1") (pinfunction "1_1") (pintype "passive"))
    )
    (net (code "17") (name "INT") (class "Default")
      (node (ref "IMU") (pin "7") (pinfunction "INT1_7") (pintype "passive"))
    )
    (net (code "18") (name "LED1") (class "Default")
      (node (ref "R_LD1") (pin "2") (pinfunction "2_2") (pintype "passive"))
    )
    (net (code "19") (name "LED2") (class "Default")
      (node (ref "R_LD2") (pin "2") (pinfunction "2_2") (pintype "passive"))
    )
    (net (code "20") (name "LED3") (class "Default")
      (node (ref "R_LD3") (pin "2") (pinfunction "2_2") (pintype "passive"))
    )
    (net (code "21") (name "LED4") (class "Default")
      (node (ref "R_LD4") (pin "2") (pinfunction "2_2") (pintype "passive"))
    )
    (net (code "22") (name "LED5") (class "Default")
      (node (ref "R_LD5") (pin "2") (pinfunction "2_2") (pintype "passive"))
    )
    (net (code "23") (name "LED6") (class "Default")
      (node (ref "R_LD6") (pin "2") (pinfunction "2_2") (pintype "passive"))
    )
    (net (code "24") (name "LED7") (class "Default")
      (node (ref "R_LD7") (pin "2") (pinfunction "2_2") (pintype "passive"))
    )
    (net (code "25") (name "LED8") (class "Default")
      (node (ref "R_LD8") (pin "2") (pinfunction "2_2") (pintype "passive"))
    )
    (net (code "26") (name "LED9") (class "Default")
      (node (ref "R_LD9") (pin "2") (pinfunction "2_2") (pintype "passive"))
    )
    (net (code "27") (name "LED10") (class "Default")
      (node (ref "R_LD10") (pin "2") (pinfunction "2_2") (pintype "passive"))
    )
    (net (code "28") (name "LED11") (class "Default")
      (node (ref "R_LD11") (pin "2") (pinfunction "2_2") (pintype "passive"))
    )
    (net (code "29") (name "LF_EMITTER") (class "Default")
      (node (ref "QE_LF") (pin "1") (pinfunction "G_1") (pintype "passive"))
      (node (ref "R_LF2") (pin "2") (pinfunction "2_2") (pintype "passive"))
    )
    (net (code "30") (name "LF_RECEIVER") (class "Default")
      (node (ref "QR_LF") (pin "1") (pinfunction "E_1") (pintype "passive"))
      (node (ref "R_LF") (pin "2") (pinfunction "2_2") (pintype "passive"))
    )
    (net (code "31") (name "L_EMITTER") (class "Default")
      (node (ref "QE_L") (pin "1") (pinfunction "G_1") (pintype "passive"))
      (node (ref "R_L2") (pin "2") (pinfunction "2_2") (pintype "passive"))
    )
    (net (code "32") (name "L_RECEIVER") (class "Default")
      (node (ref "QR_L") (pin "1") (pinfunction "E_1") (pintype "passive"))
      (node (ref "R_L") (pin "2") (pinfunction "2_2") (pintype "passive"))
    )
    (net (code "33") (name "MISO") (class "Default")
      (node (ref "IMU") (pin "4") (pinfunction "SDO/SA0_4") (pintype "passive"))
    )
    (net (code "34") (name "MOSI") (class "Default")
      (node (ref "IMU") (pin "3") (pinfunction "SDA/SDI/SDO_3") (pintype "passive"))
    )
    (net (code "35") (name "MT_RECEIVER") (class "Default")
      (node (ref "QR_MT") (pin "1") (pinfunction "E_1") (pintype "passive"))
      (node (ref "R_MT") (pin "2") (pinfunction "2_2") (pintype "passive"))
    )
    (net (code "36") (name "Net-(BOOT-Pad1)") (class "Default")
      (node (ref "BOOT") (pin "1") (pinfunction "1_1") (pintype "passive"))
      (node (ref "R_BT1") (pin "2") (pinfunction "2_2") (pintype "passive"))
      (node (ref "R_BT2") (pin "2") (pinfunction "2_2") (pintype "passive"))
    )
    (net (code "37") (name "Net-(BZ--)") (class "Default")
      (node (ref "BZ") (pin "1") (pinfunction "-_1") (pintype "passive"))
      (node (ref "D-BZ") (pin "2") (pinfunction "A_2") (pintype "passive"))
      (node (ref "Q_BZ") (pin "3") (pinfunction "D_3") (pintype "passive"))
    )
    (net (code "38") (name "Net-(D_D1-K)") (class "Default")
      (node (ref "D_D1") (pin "1") (pinfunction "K_1") (pintype "passive"))
      (node (ref "D_D2") (pin "2") (pinfunction "A_2") (pintype "passive"))
    )
    (net (code "39") (name "Net-(D_D2-K)") (class "Default")
      (node (ref "D_D2") (pin "1") (pinfunction "K_1") (pintype "passive"))
      (node (ref "R_D1") (pin "1") (pinfunction "1_1") (pintype "passive"))
      (node (ref "R_D2") (pin "1") (pinfunction "1_1") (pintype "passive"))
    )
    (net (code "40") (name "Net-(D_L-K)") (class "Default")
      (node (ref "D_L") (pin "1") (pinfunction "K_1") (pintype "passive"))
      (node (ref "R_L1") (pin "1") (pinfunction "1_1") (pintype "passive"))
    )
    (net (code "41") (name "Net-(D_LF-K)") (class "Default")
      (node (ref "D_LF") (pin "1") (pinfunction "K_1") (pintype "passive"))
      (node (ref "R_LF1") (pin "1") (pinfunction "1_1") (pintype "passive"))
    )
    (net (code "42") (name "Net-(D_R-K)") (class "Default")
      (node (ref "D_R") (pin "1") (pinfunction "K_1") (pintype "passive"))
      (node (ref "R_R1") (pin "1") (pinfunction "1_1") (pintype "passive"))
    )
    (net (code "43") (name "Net-(D_RF-K)") (class "Default")
      (node (ref "D_RF") (pin "1") (pinfunction "K_1") (pintype "passive"))
      (node (ref "R_RF1") (pin "1") (pinfunction "1_1") (pintype "passive"))
    )
    (net (code "44") (name "Net-(IMU-CAP)") (class "Default")
      (node (ref "C_IMU3") (pin "1") (pinfunction "1_1") (pintype "passive"))
      (node (ref "IMU") (pin "14") (pinfunction "CAP_14") (pintype "passive"))
    )
    (net (code "45") (name "Net-(LED1-A)") (class "Default")
      (node (ref "LED1") (pin "2") (pinfunction "A_2") (pintype "passive"))
      (node (ref "R_LD1") (pin "1") (pinfunction "1_1") (pintype "passive"))
    )
    (net (code "46") (name "Net-(LED2-A)") (class "Default")
      (node (ref "LED2") (pin "2") (pinfunction "A_2") (pintype "passive"))
      (node (ref "R_LD2") (pin "1") (pinfunction "1_1") (pintype "passive"))
    )
    (net (code "47") (name "Net-(LED3-A)") (class "Default")
      (node (ref "LED3") (pin "2") (pinfunction "A_2") (pintype "passive"))
      (node (ref "R_LD3") (pin "1") (pinfunction "1_1") (pintype "passive"))
    )
    (net (code "48") (name "Net-(LED4-A)") (class "Default")
      (node (ref "LED4") (pin "2") (pinfunction "A_2") (pintype "passive"))
      (node (ref "R_LD4") (pin "1") (pinfunction "1_1") (pintype "passive"))
    )
    (net (code "49") (name "Net-(LED5-A)") (class "Default")
      (node (ref "LED5") (pin "2") (pinfunction "A_2") (pintype "passive"))
      (node (ref "R_LD5") (pin "1") (pinfunction "1_1") (pintype "passive"))
    )
    (net (code "50") (name "Net-(LED6-A)") (class "Default")
      (node (ref "LED6") (pin "2") (pinfunction "A_2") (pintype "passive"))
      (node (ref "R_LD6") (pin "1") (pinfunction "1_1") (pintype "passive"))
    )
    (net (code "51") (name "Net-(LED7-A)") (class "Default")
      (node (ref "LED7") (pin "2") (pinfunction "A_2") (pintype "passive"))
      (node (ref "R_LD7") (pin "1") (pinfunction "1_1") (pintype "passive"))
    )
    (net (code "52") (name "Net-(LED8-A)") (class "Default")
      (node (ref "LED8") (pin "2") (pinfunction "A_2") (pintype "passive"))
      (node (ref "R_LD8") (pin "1") (pinfunction "1_1") (pintype "passive"))
    )
    (net (code "53") (name "Net-(LED9-A)") (class "Default")
      (node (ref "LED9") (pin "2") (pinfunction "A_2") (pintype "passive"))
      (node (ref "R_LD9") (pin "1") (pinfunction "1_1") (pintype "passive"))
    )
    (net (code "54") (name "Net-(LED10-A)") (class "Default")
      (node (ref "LED10") (pin "2") (pinfunction "A_2") (pintype "passive"))
      (node (ref "R_LD10") (pin "1") (pinfunction "1_1") (pintype "passive"))
    )
    (net (code "55") (name "Net-(LED11-A)") (class "Default")
      (node (ref "LED11") (pin "2") (pinfunction "A_2") (pintype "passive"))
      (node (ref "R_LD11") (pin "1") (pinfunction "1_1") (pintype "passive"))
    )
    (net (code "56") (name "Net-(QE_D-D)") (class "Default")
      (node (ref "QE_D") (pin "3") (pinfunction "D_3") (pintype "passive"))
      (node (ref "R_D1") (pin "2") (pinfunction "2_2") (pintype "passive"))
      (node (ref "R_D2") (pin "2") (pinfunction "2_2") (pintype "passive"))
    )
    (net (code "57") (name "Net-(QE_L-D)") (class "Default")
      (node (ref "QE_L") (pin "3") (pinfunction "D_3") (pintype "passive"))
      (node (ref "R_L1") (pin "2") (pinfunction "2_2") (pintype "passive"))
    )
    (net (code "58") (name "Net-(QE_LF-D)") (class "Default")
      (node (ref "QE_LF") (pin "3") (pinfunction "D_3") (pintype "passive"))
      (node (ref "R_LF1") (pin "2") (pinfunction "2_2") (pintype "passive"))
    )
    (net (code "59") (name "Net-(QE_R-D)") (class "Default")
      (node (ref "QE_R") (pin "3") (pinfunction "D_3") (pintype "passive"))
      (node (ref "R_R1") (pin "2") (pinfunction "2_2") (pintype "passive"))
    )
    (net (code "60") (name "Net-(QE_RF-D)") (class "Default")
      (node (ref "QE_RF") (pin "3") (pinfunction "D_3") (pintype "passive"))
      (node (ref "R_RF1") (pin "2") (pinfunction "2_2") (pintype "passive"))
    )
    (net (code "61") (name "RESET") (class "Default")
      (node (ref "C_RST") (pin "2") (pinfunction "2_2") (pintype "passive"))
      (node (ref "RST") (pin "2") (pinfunction "2_2") (pintype "passive"))
      (node (ref "R_RST") (pin "1") (pinfunction "1_1") (pintype "passive"))
    )
    (net (code "62") (name "RF_EMITTER") (class "Default")
      (node (ref "QE_RF") (pin "1") (pinfunction "G_1") (pintype "passive"))
      (node (ref "R_RF2") (pin "2") (pinfunction "2_2") (pintype "passive"))
    )
    (net (code "63") (name "RF_RECEIVER") (class "Default")
      (node (ref "QR_RF") (pin "1") (pinfunction "E_1") (pintype "passive"))
      (node (ref "R_RF") (pin "2") (pinfunction "2_2") (pintype "passive"))
    )
    (net (code "64") (name "R_EMITTER") (class "Default")
      (node (ref "QE_R") (pin "1") (pinfunction "G_1") (pintype "passive"))
      (node (ref "R_R2") (pin "2") (pinfunction "2_2") (pintype "passive"))
    )
    (net (code "65") (name "R_RECEIVER") (class "Default")
      (node (ref "QR_R") (pin "1") (pinfunction "E_1") (pintype "passive"))
      (node (ref "R_R") (pin "2") (pinfunction "2_2") (pintype "passive"))
    )
    (net (code "66") (name "SCK") (class "Default")
      (node (ref "IMU") (pin "2") (pinfunction "SCL/SPC_2") (pintype "passive"))
    )
    (net (code "67") (name "SCL") (class "Default")
      (node (ref "DATA") (pin "5") (pinfunction "5_5") (pintype "passive"))
    )
    (net (code "68") (name "SDA") (class "Default")
      (node (ref "DATA") (pin "7") (pinfunction "7_7") (pintype "passive"))
    )
    (net (code "69") (name "TB") (class "Default")
      (node (ref "MODE") (pin "1") (pinfunction "1_1") (pintype "passive"))
      (node (ref "R_MD") (pin "2") (pinfunction "2_2") (pintype "passive"))
    )
  )
)
